# PC-FX.net
KiCad netlist of a schematic drawn in EAGLE
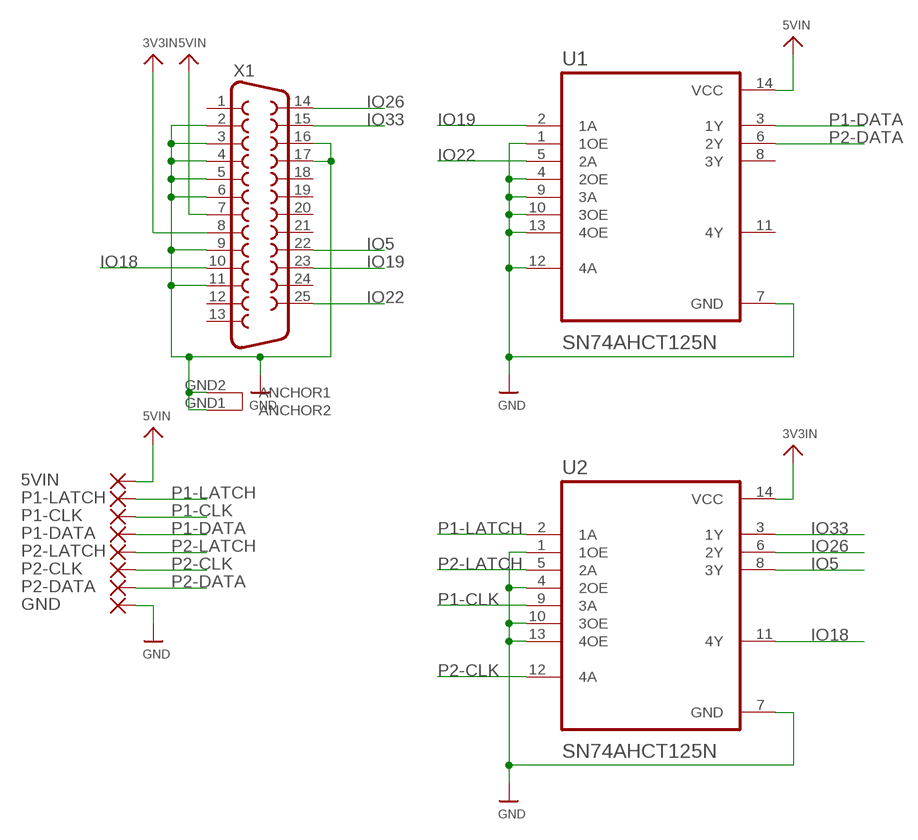
[diagram p0: schematic, sheet 1]

(export (version "E")
  (design (tool "Eeschema 10.0.6"))
  (components
    (comp (ref "5VIN")
      (value "SMD5")
      (footprint "eagle-import:SMD2,54-5,08")
      (libsource (lib "eagle-import") (part "SMD5"))
    )
    (comp (ref "GND")
      (value "SMD5")
      (footprint "eagle-import:SMD2,54-5,08")
      (libsource (lib "eagle-import") (part "SMD5"))
    )
    (comp (ref "P1-CLK")
      (value "SMD5")
      (footprint "eagle-import:SMD2,54-5,08")
      (libsource (lib "eagle-import") (part "SMD5"))
    )
    (comp (ref "P1-DATA")
      (value "SMD5")
      (footprint "eagle-import:SMD2,54-5,08")
      (libsource (lib "eagle-import") (part "SMD5"))
    )
    (comp (ref "P1-LATCH")
      (value "SMD5")
      (footprint "eagle-import:SMD2,54-5,08")
      (libsource (lib "eagle-import") (part "SMD5"))
    )
    (comp (ref "P2-CLK")
      (value "SMD5")
      (footprint "eagle-import:SMD2,54-5,08")
      (libsource (lib "eagle-import") (part "SMD5"))
    )
    (comp (ref "P2-DATA")
      (value "SMD5")
      (footprint "eagle-import:SMD2,54-5,08")
      (libsource (lib "eagle-import") (part "SMD5"))
    )
    (comp (ref "P2-LATCH")
      (value "SMD5")
      (footprint "eagle-import:SMD2,54-5,08")
      (libsource (lib "eagle-import") (part "SMD5"))
    )
    (comp (ref "U1")
      (value "SN74AHCT125N")
      (footprint "eagle-import:DIP794W45P254L1969H508Q14")
      (fields (field (name "MF") "Texas Instruments"))
      (libsource (lib "eagle-import") (part "SN74AHCT125N"))
    )
    (comp (ref "U2")
      (value "SN74AHCT125N")
      (footprint "eagle-import:DIP794W45P254L1969H508Q14")
      (fields (field (name "MF") "Texas Instruments"))
      (libsource (lib "eagle-import") (part "SN74AHCT125N"))
    )
    (comp (ref "X1")
      (value "DB25_FEMALEHP")
      (footprint "eagle-import:F25HP")
      (libsource (lib "eagle-import") (part "DB25_FEMALEHP"))
    )
  )
  (nets
    (net (code "1") (name "/IO5") (class "Default")
      (node (ref "U2") (pin "8") (pinfunction "3Y_8") (pintype "output"))
      (node (ref "X1") (pin "22") (pinfunction "22_22") (pintype "passive"))
    )
    (net (code "2") (name "/IO18") (class "Default")
      (node (ref "U2") (pin "11") (pinfunction "4Y_11") (pintype "output"))
      (node (ref "X1") (pin "10") (pinfunction "10_10") (pintype "passive"))
    )
    (net (code "3") (name "/IO19") (class "Default")
      (node (ref "U1") (pin "2") (pinfunction "1A_2") (pintype "input"))
      (node (ref "X1") (pin "23") (pinfunction "23_23") (pintype "passive"))
    )
    (net (code "4") (name "/IO22") (class "Default")
      (node (ref "U1") (pin "5") (pinfunction "2A_5") (pintype "input"))
      (node (ref "X1") (pin "25") (pinfunction "25_25") (pintype "passive"))
    )
    (net (code "5") (name "/IO26") (class "Default")
      (node (ref "U2") (pin "6") (pinfunction "2Y_6") (pintype "output"))
      (node (ref "X1") (pin "14") (pinfunction "14_14") (pintype "passive"))
    )
    (net (code "6") (name "/IO33") (class "Default")
      (node (ref "U2") (pin "3") (pinfunction "1Y_3") (pintype "output"))
      (node (ref "X1") (pin "15") (pinfunction "15_15") (pintype "passive"))
    )
    (net (code "7") (name "/P1-CLK") (class "Default")
      (node (ref "P1-CLK") (pin "1") (pinfunction "P_1") (pintype "passive"))
      (node (ref "U2") (pin "9") (pinfunction "3A_9") (pintype "input"))
    )
    (net (code "8") (name "/P1-DATA") (class "Default")
      (node (ref "P1-DATA") (pin "1") (pinfunction "P_1") (pintype "passive"))
      (node (ref "U1") (pin "3") (pinfunction "1Y_3") (pintype "output"))
    )
    (net (code "9") (name "/P1-LATCH") (class "Default")
      (node (ref "P1-LATCH") (pin "1") (pinfunction "P_1") (pintype "passive"))
      (node (ref "U2") (pin "2") (pinfunction "1A_2") (pintype "input"))
    )
    (net (code "10") (name "/P2-CLK") (class "Default")
      (node (ref "P2-CLK") (pin "1") (pinfunction "P_1") (pintype "passive"))
      (node (ref "U2") (pin "12") (pinfunction "4A_12") (pintype "bidirectional"))
    )
    (net (code "11") (name "/P2-DATA") (class "Default")
      (node (ref "P2-DATA") (pin "1") (pinfunction "P_1") (pintype "passive"))
      (node (ref "U1") (pin "6") (pinfunction "2Y_6") (pintype "output"))
    )
    (net (code "12") (name "/P2-LATCH") (class "Default")
      (node (ref "P2-LATCH") (pin "1") (pinfunction "P_1") (pintype "passive"))
      (node (ref "U2") (pin "5") (pinfunction "2A_5") (pintype "input"))
    )
    (net (code "13") (name "3V3IN") (class "Default")
      (node (ref "U2") (pin "14") (pinfunction "VCC_14") (pintype "power_in"))
      (node (ref "X1") (pin "8") (pinfunction "8_8") (pintype "passive"))
    )
    (net (code "14") (name "5VIN") (class "Default")
      (node (ref "5VIN") (pin "1") (pinfunction "P_1") (pintype "passive"))
      (node (ref "U1") (pin "14") (pinfunction "VCC_14") (pintype "power_in"))
      (node (ref "X1") (pin "7") (pinfunction "7_7") (pintype "passive"))
    )
    (net (code "15") (name "GND") (class "Default")
      (node (ref "GND") (pin "1") (pinfunction "P_1") (pintype "passive"))
      (node (ref "U1") (pin "1") (pinfunction "1OE_1") (pintype "input"))
      (node (ref "U1") (pin "10") (pinfunction "3OE_10") (pintype "input"))
      (node (ref "U1") (pin "12") (pinfunction "4A_12") (pintype "bidirectional"))
      (node (ref "U1") (pin "13") (pinfunction "4OE_13") (pintype "input"))
      (node (ref "U1") (pin "4") (pinfunction "2OE_4") (pintype "input"))
      (node (ref "U1") (pin "7") (pinfunction "GND_7") (pintype "power_in"))
      (node (ref "U1") (pin "9") (pinfunction "3A_9") (pintype "input"))
      (node (ref "U2") (pin "1") (pinfunction "1OE_1") (pintype "input"))
      (node (ref "U2") (pin "10") (pinfunction "3OE_10") (pintype "input"))
      (node (ref "U2") (pin "13") (pinfunction "4OE_13") (pintype "input"))
      (node (ref "U2") (pin "4") (pinfunction "2OE_4") (pintype "input"))
      (node (ref "U2") (pin "7") (pinfunction "GND_7") (pintype "power_in"))
      (node (ref "X1") (pin "11") (pinfunction "11_11") (pintype "passive"))
      (node (ref "X1") (pin "16") (pinfunction "16_16") (pintype "passive"))
      (node (ref "X1") (pin "17") (pinfunction "17_17") (pintype "passive"))
      (node (ref "X1") (pin "2") (pinfunction "2_2") (pintype "passive"))
      (node (ref "X1") (pin "3") (pinfunction "3_3") (pintype "passive"))
      (node (ref "X1") (pin "4") (pinfunction "4_4") (pintype "passive"))
      (node (ref "X1") (pin "5") (pinfunction "5_5") (pintype "passive"))
      (node (ref "X1") (pin "6") (pinfunction "6_6") (pintype "passive"))
      (node (ref "X1") (pin "9") (pinfunction "9_9") (pintype "passive"))
      (node (ref "X1") (pin "GND1") (pinfunction "ANCHOR2_GND1") (pintype "bidirectional"))
      (node (ref "X1") (pin "GND2") (pinfunction "ANCHOR1_GND2") (pintype "bidirectional"))
    )
    (net (code "16") (name "unconnected-(U1-3Y-Pad8)") (class "Default")
      (node (ref "U1") (pin "8") (pinfunction "3Y_8") (pintype "output"))
    )
    (net (code "17") (name "unconnected-(U1-4Y-Pad11)") (class "Default")
      (node (ref "U1") (pin "11") (pinfunction "4Y_11") (pintype "output"))
    )
    (net (code "18") (name "unconnected-(X1-Pad1)") (class "Default")
      (node (ref "X1") (pin "1") (pinfunction "1_1") (pintype "passive"))
    )
    (net (code "19") (name "unconnected-(X1-Pad12)") (class "Default")
      (node (ref "X1") (pin "12") (pinfunction "12_12") (pintype "passive"))
    )
    (net (code "20") (name "unconnected-(X1-Pad13)") (class "Default")
      (node (ref "X1") (pin "13") (pinfunction "13_13") (pintype "passive"))
    )
    (net (code "21") (name "unconnected-(X1-Pad18)") (class "Default")
      (node (ref "X1") (pin "18") (pinfunction "18_18") (pintype "passive"))
    )
    (net (code "22") (name "unconnected-(X1-Pad19)") (class "Default")
      (node (ref "X1") (pin "19") (pinfunction "19_19") (pintype "passive"))
    )
    (net (code "23") (name "unconnected-(X1-Pad20)") (class "Default")
      (node (ref "X1") (pin "20") (pinfunction "20_20") (pintype "passive"))
    )
    (net (code "24") (name "unconnected-(X1-Pad21)") (class "Default")
      (node (ref "X1") (pin "21") (pinfunction "21_21") (pintype "passive"))
    )
    (net (code "25") (name "unconnected-(X1-Pad24)") (class "Default")
      (node (ref "X1") (pin "24") (pinfunction "24_24") (pintype "passive"))
    )
  )
)
